# brew_schematic.net
KiCad netlist of a schematic drawn in Altium Designer
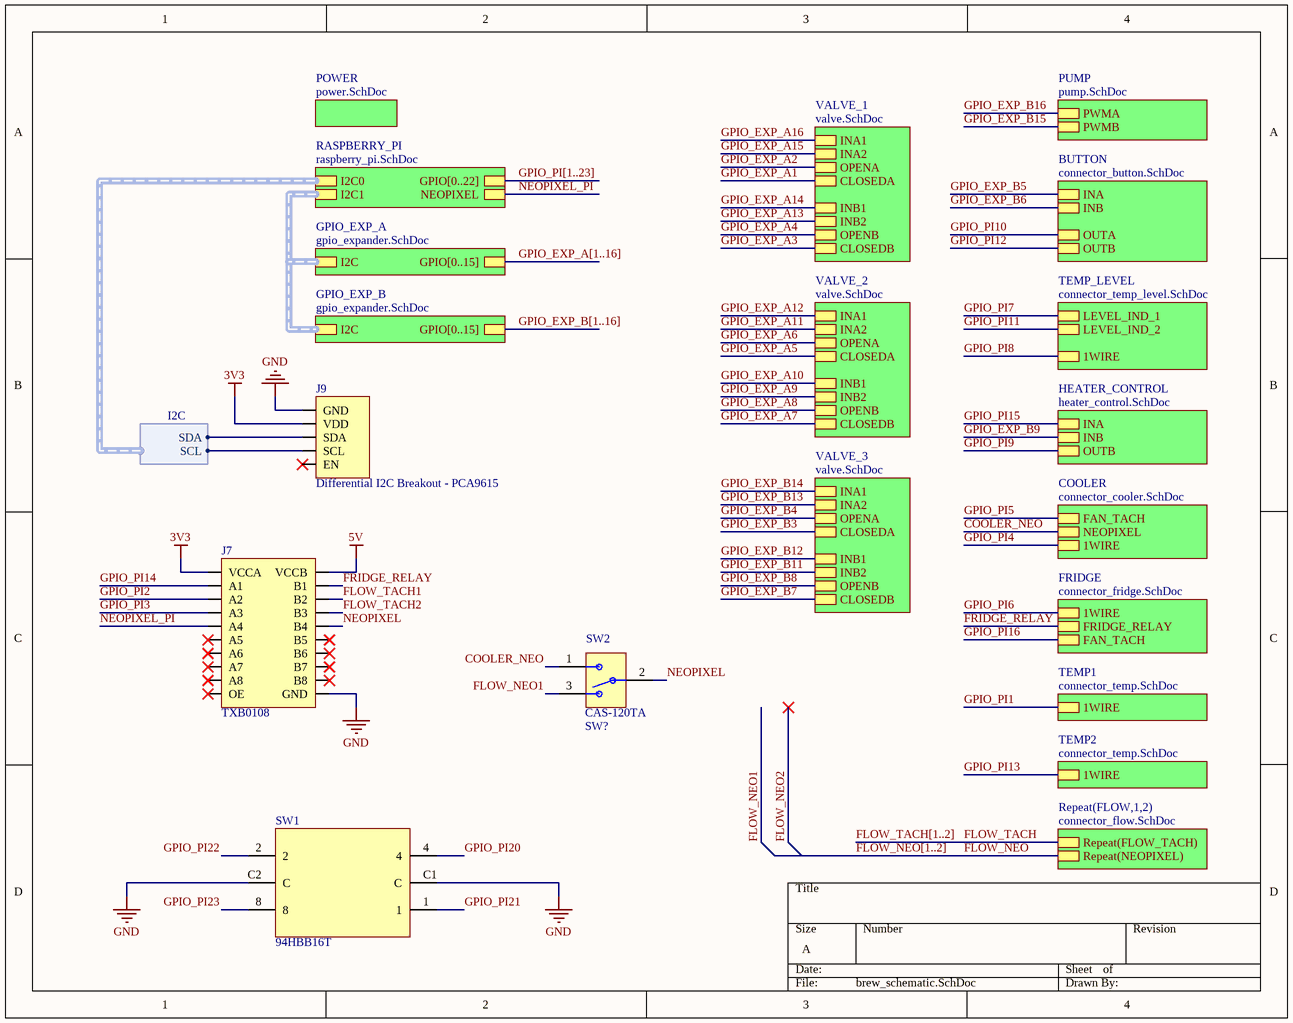
[diagram p0: brew_schematic.SchDoc]

(export (version "E")
  (design (tool "Eeschema 10.0.6"))
  (components
    (comp (ref "J7") (value "TXB0108") (footprint "TXB0108") (libsource (lib "brew_lib") (part "TXB0108")))
    (comp (ref "J9")
      (value "Differential I2C Breakout - PCA9615")
      (footprint "Differential I2C Breakout - PCA9615")
      (libsource (lib "brew_lib") (part "Differential I2C Breakout - PCA9615"))
    )
    (comp (ref "SW1")
      (value "SWITCH_HEX ROTARY_50V_DIP16")
      (footprint "SW_HEX_ROTARY_94HBB16T")
      (description "SWITCH ROTARY DIP HEX 100MA 50V")
      (fields (field (name "MFG") "GRAYHILL") (field (name "MFG P/N") "94HBB16T"))
      (libsource (lib "AltiumReleaseLibDB") (part "SWITCH_HEX ROTARY_50V_DIP16"))
    )
    (comp (ref "SW2")
      (value "SWITCH_DIP_SPDT_CAS-120TA")
      (footprint "SWITCH_CAS-120TA")
      (description "SLIDE SWITCH SPDT J HOOK 6V")
      (fields
        (field (name "MFG") "Copal Electronics Inc")
        (field (name "MFG P/N") "CAS-120TA")
        (field (name "DESIGNATOR") "SW?")
      )
      (libsource (lib "AltiumReleaseLibDB") (part "SWITCH_DIP_SPDT_CAS-120TA"))
    )
  )
  (nets
    (net (code "8") (name "/COOLER_NEO") (class "Default") (node (ref "SW2") (pin "1") (pintype "passive")))
    (net (code "10") (name "/FLOW_NEO1") (class "Default") (node (ref "SW2") (pin "3") (pintype "passive")))
    (net (code "14") (name "/FLOW_TACH1") (class "Default")
      (node (ref "J7") (pin "18") (pinfunction "B2_18") (pintype "passive"))
    )
    (net (code "15") (name "/FLOW_TACH2") (class "Default")
      (node (ref "J7") (pin "17") (pinfunction "B3_17") (pintype "passive"))
    )
    (net (code "17") (name "/FRIDGE_RELAY") (class "Default")
      (node (ref "J7") (pin "19") (pinfunction "B1_19") (pintype "passive"))
    )
    (net (code "50") (name "/GPIO_PI2") (class "Default")
      (node (ref "J7") (pin "3") (pinfunction "A2_3") (pintype "passive"))
    )
    (net (code "51") (name "/GPIO_PI3") (class "Default")
      (node (ref "J7") (pin "4") (pinfunction "A3_4") (pintype "passive"))
    )
    (net (code "62") (name "/GPIO_PI14") (class "Default")
      (node (ref "J7") (pin "2") (pinfunction "A1_2") (pintype "passive"))
    )
    (net (code "65") (name "/GPIO_PI20") (class "Default")
      (node (ref "SW1") (pin "4") (pinfunction "4_4") (pintype "passive"))
    )
    (net (code "66") (name "/GPIO_PI21") (class "Default")
      (node (ref "SW1") (pin "1") (pinfunction "1_1") (pintype "passive"))
    )
    (net (code "67") (name "/GPIO_PI22") (class "Default")
      (node (ref "SW1") (pin "2") (pinfunction "2_2") (pintype "passive"))
    )
    (net (code "68") (name "/GPIO_PI23") (class "Default")
      (node (ref "SW1") (pin "8") (pinfunction "8_8") (pintype "passive"))
    )
    (net (code "71") (name "/NEOPIXEL") (class "Default")
      (node (ref "J7") (pin "16") (pinfunction "B4_16") (pintype "passive"))
      (node (ref "SW2") (pin "2") (pintype "passive"))
    )
    (net (code "72") (name "/NEOPIXEL_PI") (class "Default")
      (node (ref "J7") (pin "5") (pinfunction "A4_5") (pintype "passive"))
    )
    (net (code "73") (name "/SCL") (class "Default")
      (node (ref "J9") (pin "4") (pinfunction "SCL_4") (pintype "passive"))
    )
    (net (code "74") (name "/SDA") (class "Default")
      (node (ref "J9") (pin "3") (pinfunction "SDA_3") (pintype "passive"))
    )
    (net (code "76") (name "3V3") (class "Default")
      (node (ref "J7") (pin "1") (pinfunction "VCCA_1") (pintype "passive"))
      (node (ref "J9") (pin "2") (pinfunction "VDD_2") (pintype "passive"))
    )
    (net (code "77") (name "5V") (class "Default")
      (node (ref "J7") (pin "20") (pinfunction "VCCB_20") (pintype "passive"))
    )
    (net (code "78") (name "GND") (class "Default")
      (node (ref "J7") (pin "11") (pinfunction "GND_11") (pintype "passive"))
      (node (ref "J9") (pin "1") (pinfunction "GND_1") (pintype "passive"))
      (node (ref "SW1") (pin "C1") (pinfunction "C_C1") (pintype "passive"))
      (node (ref "SW1") (pin "C2") (pinfunction "C_C2") (pintype "passive"))
    )
    (net (code "79") (name "unconnected-(J7-A5-Pad6)") (class "Default")
      (node (ref "J7") (pin "6") (pinfunction "A5_6") (pintype "passive+no_connect"))
    )
    (net (code "80") (name "unconnected-(J7-A6-Pad7)") (class "Default")
      (node (ref "J7") (pin "7") (pinfunction "A6_7") (pintype "passive+no_connect"))
    )
    (net (code "81") (name "unconnected-(J7-A7-Pad8)") (class "Default")
      (node (ref "J7") (pin "8") (pinfunction "A7_8") (pintype "passive+no_connect"))
    )
    (net (code "82") (name "unconnected-(J7-A8-Pad9)") (class "Default")
      (node (ref "J7") (pin "9") (pinfunction "A8_9") (pintype "passive+no_connect"))
    )
    (net (code "83") (name "unconnected-(J7-B5-Pad15)") (class "Default")
      (node (ref "J7") (pin "15") (pinfunction "B5_15") (pintype "passive+no_connect"))
    )
    (net (code "84") (name "unconnected-(J7-B6-Pad14)") (class "Default")
      (node (ref "J7") (pin "14") (pinfunction "B6_14") (pintype "passive+no_connect"))
    )
    (net (code "85") (name "unconnected-(J7-B7-Pad13)") (class "Default")
      (node (ref "J7") (pin "13") (pinfunction "B7_13") (pintype "passive+no_connect"))
    )
    (net (code "86") (name "unconnected-(J7-B8-Pad12)") (class "Default")
      (node (ref "J7") (pin "12") (pinfunction "B8_12") (pintype "passive+no_connect"))
    )
    (net (code "87") (name "unconnected-(J7-OE-Pad10)") (class "Default")
      (node (ref "J7") (pin "10") (pinfunction "OE_10") (pintype "passive+no_connect"))
    )
    (net (code "88") (name "unconnected-(J9-EN-Pad5)") (class "Default")
      (node (ref "J9") (pin "5") (pinfunction "EN_5") (pintype "passive+no_connect"))
    )
  )
)
